# main.net
KiCad netlist of a schematic drawn in Altium Designer
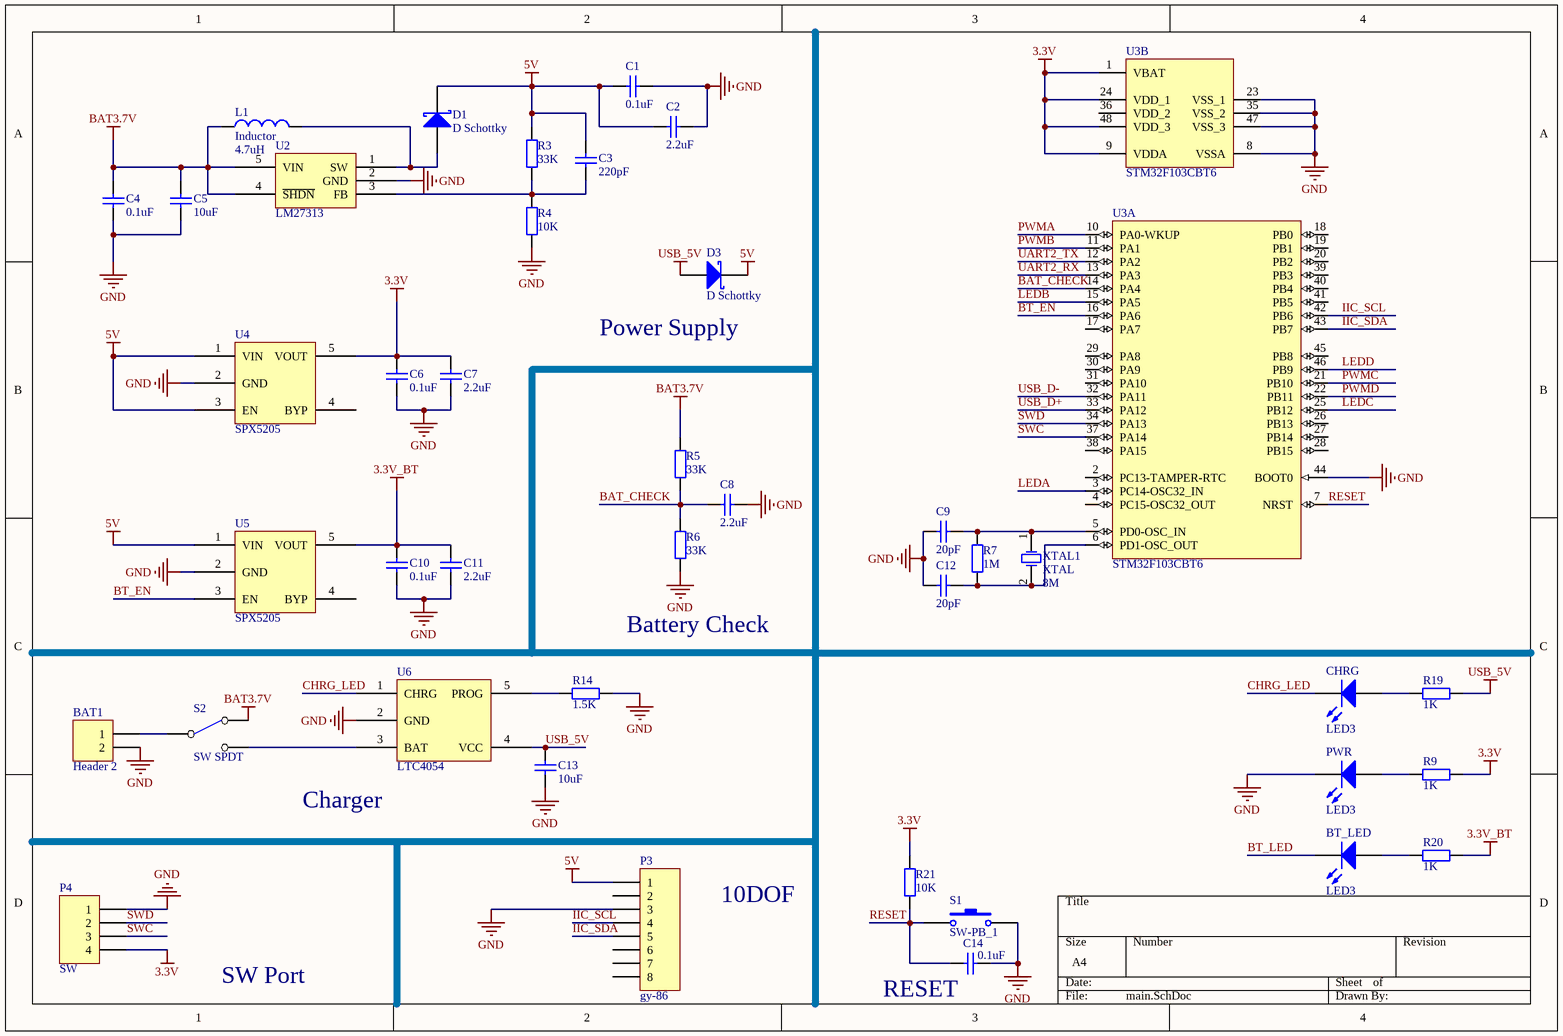
[diagram p0: main.SchDoc]

(export (version "E")
  (design (tool "Eeschema 10.0.6"))
  (components
    (comp (ref "BAT1")
      (value "Header 2")
      (footprint "HDR1*2 battery")
      (description "Header, 2-Pin")
      (fields (field (name "PUBLISHER") "Altium Limited"))
      (libsource (lib "Miscellaneous Connectors") (part "Header 2"))
    )
    (comp (ref "BT_LED")
      (value "LED3")
      (footprint "LED_0603_RED")
      (description "Typical BLUE SiC LED")
      (fields (field (name "PUBLISHER") "Altium Limited"))
      (libsource (lib "Miscellaneous Devices") (part "LED3"))
    )
    (comp (ref "C1")
      (value "0.1uF")
      (footprint "C-0603")
      (description "Capacitor (Semiconductor SIM Model)")
      (fields (field (name "Comment") "Cap Semi") (field (name "PUBLISHER") "Altium Limited"))
      (libsource (lib "Miscellaneous Devices") (part "Cap Semi"))
    )
    (comp (ref "C2")
      (value "2.2uF")
      (footprint "C-0603")
      (description "Capacitor (Semiconductor SIM Model)")
      (fields (field (name "Comment") "Cap Semi") (field (name "PUBLISHER") "Altium Limited"))
      (libsource (lib "Miscellaneous Devices") (part "Cap Semi"))
    )
    (comp (ref "C3")
      (value "220pF")
      (footprint "C-0603")
      (description "Capacitor (Semiconductor SIM Model)")
      (fields (field (name "Comment") "Cap Semi") (field (name "PUBLISHER") "Altium Limited"))
      (libsource (lib "Miscellaneous Devices") (part "Cap Semi"))
    )
    (comp (ref "C4")
      (value "0.1uF")
      (footprint "C-0603")
      (description "Capacitor (Semiconductor SIM Model)")
      (fields (field (name "Comment") "Cap Semi") (field (name "PUBLISHER") "Altium Limited"))
      (libsource (lib "Miscellaneous Devices") (part "Cap Semi"))
    )
    (comp (ref "C5")
      (value "10uF")
      (footprint "C-0603")
      (description "Capacitor (Semiconductor SIM Model)")
      (fields (field (name "Comment") "Cap Semi") (field (name "PUBLISHER") "Altium Limited"))
      (libsource (lib "Miscellaneous Devices") (part "Cap Semi"))
    )
    (comp (ref "C6")
      (value "0.1uF")
      (footprint "C-0603")
      (description "Capacitor (Semiconductor SIM Model)")
      (fields (field (name "Comment") "Cap Semi") (field (name "PUBLISHER") "Altium Limited"))
      (libsource (lib "Miscellaneous Devices") (part "Cap Semi"))
    )
    (comp (ref "C7")
      (value "2.2uF")
      (footprint "C-0603")
      (description "Capacitor (Semiconductor SIM Model)")
      (fields (field (name "Comment") "Cap Semi") (field (name "PUBLISHER") "Altium Limited"))
      (libsource (lib "Miscellaneous Devices") (part "Cap Semi"))
    )
    (comp (ref "C8")
      (value "2.2uF")
      (footprint "C-0603")
      (description "Capacitor (Semiconductor SIM Model)")
      (fields (field (name "Comment") "Cap Semi") (field (name "PUBLISHER") "Altium Limited"))
      (libsource (lib "Miscellaneous Devices") (part "Cap Semi"))
    )
    (comp (ref "C9")
      (value "20pF")
      (footprint "C-0603")
      (description "Capacitor (Semiconductor SIM Model)")
      (fields (field (name "Comment") "Cap") (field (name "PUBLISHER") "Altium Limited"))
      (libsource (lib "Miscellaneous Devices") (part "Cap Semi"))
    )
    (comp (ref "C10")
      (value "0.1uF")
      (footprint "C-0603")
      (description "Capacitor (Semiconductor SIM Model)")
      (fields (field (name "Comment") "Cap Semi") (field (name "PUBLISHER") "Altium Limited"))
      (libsource (lib "Miscellaneous Devices") (part "Cap Semi"))
    )
    (comp (ref "C11")
      (value "2.2uF")
      (footprint "C-0603")
      (description "Capacitor (Semiconductor SIM Model)")
      (fields (field (name "Comment") "Cap Semi") (field (name "PUBLISHER") "Altium Limited"))
      (libsource (lib "Miscellaneous Devices") (part "Cap Semi"))
    )
    (comp (ref "C12")
      (value "20pF")
      (footprint "C-0603")
      (description "Capacitor (Semiconductor SIM Model)")
      (fields (field (name "Comment") "Cap") (field (name "PUBLISHER") "Altium Limited"))
      (libsource (lib "Miscellaneous Devices") (part "Cap Semi"))
    )
    (comp (ref "C13")
      (value "10uF")
      (footprint "C-0603")
      (description "Capacitor (Semiconductor SIM Model)")
      (fields (field (name "Comment") "Cap Semi") (field (name "PUBLISHER") "Altium Limited"))
      (libsource (lib "Miscellaneous Devices") (part "Cap Semi"))
    )
    (comp (ref "C14")
      (value "0.1uF")
      (footprint "C-0603")
      (description "Capacitor (Semiconductor SIM Model)")
      (fields (field (name "Comment") "Cap") (field (name "PUBLISHER") "Altium Limited"))
      (libsource (lib "Miscellaneous Devices") (part "Cap Semi"))
    )
    (comp (ref "CHRG")
      (value "LED3")
      (footprint "LED_0603_RED")
      (description "Typical BLUE SiC LED")
      (fields (field (name "PUBLISHER") "Altium Limited"))
      (libsource (lib "Miscellaneous Devices") (part "LED3"))
    )
    (comp (ref "D1")
      (value "D Schottky")
      (footprint "DIODE-1206")
      (description "Schottky Diode")
      (fields (field (name "PUBLISHER") "Altium Limited"))
      (libsource (lib "Miscellaneous Devices") (part "D Schottky"))
    )
    (comp (ref "D3")
      (value "D Schottky")
      (footprint "DIODE-1206")
      (description "Schottky Diode")
      (fields (field (name "PUBLISHER") "Altium Limited"))
      (libsource (lib "Miscellaneous Devices") (part "D Schottky"))
    )
    (comp (ref "L1")
      (value "Inductor")
      (footprint "L-SMD-7")
      (fields (field (name "ALTIUM_VALUE") "4.7uH") (field (name "PUBLISHER") "Altium Limited"))
      (libsource (lib "Miscellaneous Devices") (part "Inductor"))
    )
    (comp (ref "P3")
      (value "gy-86")
      (footprint "HDR1X8")
      (description "Header, 8-Pin")
      (fields (field (name "PUBLISHER") "Altium Limited"))
      (libsource (lib "Miscellaneous Connectors") (part "Header 8"))
    )
    (comp (ref "P4")
      (value "SW")
      (footprint "HDR1X4")
      (description "Header, 4-Pin")
      (fields (field (name "PUBLISHER") "Altium Limited"))
      (libsource (lib "Miscellaneous Connectors") (part "Header 4"))
    )
    (comp (ref "PWR")
      (value "LED3")
      (footprint "LED_0603_RED")
      (description "Typical BLUE SiC LED")
      (fields (field (name "PUBLISHER") "Altium Limited"))
      (libsource (lib "Miscellaneous Devices") (part "LED3"))
    )
    (comp (ref "R3")
      (value "33K")
      (footprint "R-0603")
      (description "Resistor")
      (fields (field (name "Comment") "Res2") (field (name "PUBLISHER") "Altium Limited"))
      (libsource (lib "Miscellaneous Devices") (part "Res2"))
    )
    (comp (ref "R4")
      (value "10K")
      (footprint "R-0603")
      (description "Resistor")
      (fields (field (name "Comment") "Res2") (field (name "PUBLISHER") "Altium Limited"))
      (libsource (lib "Miscellaneous Devices") (part "Res2"))
    )
    (comp (ref "R5")
      (value "33K")
      (footprint "R-0603")
      (description "Resistor")
      (fields (field (name "Comment") "Res2") (field (name "PUBLISHER") "Altium Limited"))
      (libsource (lib "Miscellaneous Devices") (part "Res2"))
    )
    (comp (ref "R6")
      (value "33K")
      (footprint "R-0603")
      (description "Resistor")
      (fields (field (name "Comment") "Res2") (field (name "PUBLISHER") "Altium Limited"))
      (libsource (lib "Miscellaneous Devices") (part "Res2"))
    )
    (comp (ref "R7")
      (value "1M")
      (footprint "R-0603")
      (description "Resistor")
      (fields (field (name "Comment") "Res2") (field (name "PUBLISHER") "Altium Limited"))
      (libsource (lib "") (part "Res2_1"))
    )
    (comp (ref "R9")
      (value "1K")
      (footprint "R-0603")
      (description "Resistor")
      (fields (field (name "Comment") "Res2") (field (name "PUBLISHER") "Altium Limited"))
      (libsource (lib "Miscellaneous Devices") (part "Res2"))
    )
    (comp (ref "R14")
      (value "1.5K")
      (footprint "R-0603")
      (description "Resistor")
      (fields (field (name "Comment") "Res2") (field (name "PUBLISHER") "Altium Limited"))
      (libsource (lib "") (part "Res2_1"))
    )
    (comp (ref "R19")
      (value "1K")
      (footprint "R-0603")
      (description "Resistor")
      (fields (field (name "Comment") "Res2") (field (name "PUBLISHER") "Altium Limited"))
      (libsource (lib "Miscellaneous Devices") (part "Res2"))
    )
    (comp (ref "R20")
      (value "1K")
      (footprint "R-0603")
      (description "Resistor")
      (fields (field (name "Comment") "Res2") (field (name "PUBLISHER") "Altium Limited"))
      (libsource (lib "Miscellaneous Devices") (part "Res2"))
    )
    (comp (ref "R21")
      (value "10K")
      (footprint "R-0603")
      (description "Resistor")
      (fields (field (name "Comment") "Res2") (field (name "PUBLISHER") "Altium Limited"))
      (libsource (lib "") (part "Res2_2"))
    )
    (comp (ref "S1")
      (value "SW-PB_1")
      (footprint "SW-2-6*3")
      (description "Switch")
      (fields (field (name "PUBLISHER") "Altium Limited"))
      (libsource (lib "mcu_board") (part "SW-PB_1"))
    )
    (comp (ref "S2") (value "SW SPDT") (footprint "SW-SPDT 2mm") (libsource (lib "MOS_H") (part "SW SPDT")))
    (comp (ref "U2") (value "LM27313") (footprint "SOT23-5") (libsource (lib "mcu_board") (part "LM27313")))
    (comp (ref "U3")
      (value "STM32F103CBT6")
      (footprint "STM-LQFP48_M")
      (libsource (lib "STMicroelectronics STM32 F1") (part "STM32F103CBT6"))
    )
    (comp (ref "U4") (value "SPX5205") (footprint "SOT23-5") (libsource (lib "mcu_board") (part "SPX5205")))
    (comp (ref "U5") (value "SPX5205") (footprint "SOT23-5") (libsource (lib "mcu_board") (part "SPX5205")))
    (comp (ref "U6") (value "LTC4054") (footprint "SOT23-5") (libsource (lib "mcu_board") (part "LTC4054")))
    (comp (ref "XTAL1")
      (value "XTAL")
      (footprint "XTAL-QC49/SMD")
      (fields (field (name "FREQUENCE") "8M"))
      (libsource (lib "mcu_board") (part "XTAL"))
    )
  )
  (nets
    (net (code "1") (name "/BAT_CHECK") (class "Default")
      (node (ref "C8") (pin "2") (pinfunction "2_2") (pintype "passive"))
      (node (ref "R5") (pin "1") (pinfunction "1_1") (pintype "passive"))
      (node (ref "R6") (pin "2") (pinfunction "2_2") (pintype "passive"))
      (node (ref "U3") (pin "14") (pinfunction "PA4_14") (pintype "bidirectional"))
    )
    (net (code "2") (name "/BT_EN") (class "Default")
      (node (ref "U3") (pin "16") (pinfunction "PA6_16") (pintype "bidirectional"))
      (node (ref "U5") (pin "3") (pinfunction "EN_3") (pintype "passive"))
    )
    (net (code "3") (name "/BT_LED") (class "Default")
      (node (ref "BT_LED") (pin "2") (pinfunction "K_2") (pintype "passive"))
    )
    (net (code "4") (name "/CHRG_LED") (class "Default")
      (node (ref "CHRG") (pin "2") (pinfunction "K_2") (pintype "passive"))
      (node (ref "U6") (pin "1") (pinfunction "CHRG_1") (pintype "passive"))
    )
    (net (code "5") (name "/IIC_SCL") (class "Default")
      (node (ref "P3") (pin "4") (pinfunction "4_4") (pintype "passive"))
      (node (ref "U3") (pin "42") (pinfunction "PB6_42") (pintype "bidirectional"))
    )
    (net (code "6") (name "/IIC_SDA") (class "Default")
      (node (ref "P3") (pin "5") (pinfunction "5_5") (pintype "passive"))
      (node (ref "U3") (pin "43") (pinfunction "PB7_43") (pintype "bidirectional"))
    )
    (net (code "7") (name "/LEDA") (class "Default")
      (node (ref "U3") (pin "3") (pinfunction "PC14-OSC32_IN_3") (pintype "bidirectional"))
    )
    (net (code "8") (name "/LEDB") (class "Default")
      (node (ref "U3") (pin "15") (pinfunction "PA5_15") (pintype "bidirectional"))
    )
    (net (code "9") (name "/LEDC") (class "Default")
      (node (ref "U3") (pin "25") (pinfunction "PB12_25") (pintype "bidirectional"))
    )
    (net (code "10") (name "/LEDD") (class "Default")
      (node (ref "U3") (pin "46") (pinfunction "PB9_46") (pintype "bidirectional"))
    )
    (net (code "11") (name "/PWMA") (class "Default")
      (node (ref "U3") (pin "10") (pinfunction "PA0-WKUP_10") (pintype "bidirectional"))
    )
    (net (code "12") (name "/PWMB") (class "Default")
      (node (ref "U3") (pin "11") (pinfunction "PA1_11") (pintype "bidirectional"))
    )
    (net (code "13") (name "/PWMC") (class "Default")
      (node (ref "U3") (pin "21") (pinfunction "PB10_21") (pintype "bidirectional"))
    )
    (net (code "14") (name "/PWMD") (class "Default")
      (node (ref "U3") (pin "22") (pinfunction "PB11_22") (pintype "bidirectional"))
    )
    (net (code "15") (name "/RESET") (class "Default")
      (node (ref "C14") (pin "2") (pinfunction "2_2") (pintype "passive"))
      (node (ref "R21") (pin "1") (pinfunction "1_1") (pintype "passive"))
      (node (ref "S1") (pin "1") (pinfunction "1_1") (pintype "passive"))
      (node (ref "U3") (pin "7") (pinfunction "NRST_7") (pintype "bidirectional"))
    )
    (net (code "16") (name "/SWC") (class "Default")
      (node (ref "P4") (pin "3") (pinfunction "3_3") (pintype "passive"))
      (node (ref "U3") (pin "37") (pinfunction "PA14_37") (pintype "bidirectional"))
    )
    (net (code "17") (name "/SWD") (class "Default")
      (node (ref "P4") (pin "2") (pinfunction "2_2") (pintype "passive"))
      (node (ref "U3") (pin "34") (pinfunction "PA13_34") (pintype "bidirectional"))
    )
    (net (code "18") (name "/UART2_RX") (class "Default")
      (node (ref "U3") (pin "13") (pinfunction "PA3_13") (pintype "bidirectional"))
    )
    (net (code "19") (name "/UART2_TX") (class "Default")
      (node (ref "U3") (pin "12") (pinfunction "PA2_12") (pintype "bidirectional"))
    )
    (net (code "20") (name "/USB_D+") (class "Default")
      (node (ref "U3") (pin "33") (pinfunction "PA12_33") (pintype "bidirectional"))
    )
    (net (code "21") (name "/USB_D-") (class "Default")
      (node (ref "U3") (pin "32") (pinfunction "PA11_32") (pintype "bidirectional"))
    )
    (net (code "22") (name "3.3V") (class "Default")
      (node (ref "C6") (pin "1") (pinfunction "1_1") (pintype "passive"))
      (node (ref "C7") (pin "1") (pinfunction "1_1") (pintype "passive"))
      (node (ref "P4") (pin "4") (pinfunction "4_4") (pintype "power_in"))
      (node (ref "R21") (pin "2") (pinfunction "2_2") (pintype "passive"))
      (node (ref "R9") (pin "2") (pinfunction "2_2") (pintype "passive"))
      (node (ref "U3") (pin "1") (pinfunction "VBAT_1") (pintype "power_in"))
      (node (ref "U3") (pin "24") (pinfunction "VDD_1_24") (pintype "power_in"))
      (node (ref "U3") (pin "48") (pinfunction "VDD_3_48") (pintype "power_in"))
      (node (ref "U3") (pin "9") (pinfunction "VDDA_9") (pintype "power_in"))
      (node (ref "U4") (pin "5") (pinfunction "VOUT_5") (pintype "passive"))
    )
    (net (code "23") (name "3.3V_BT") (class "Default")
      (node (ref "C10") (pin "1") (pinfunction "1_1") (pintype "passive"))
      (node (ref "C11") (pin "1") (pinfunction "1_1") (pintype "passive"))
      (node (ref "R20") (pin "2") (pinfunction "2_2") (pintype "passive"))
      (node (ref "U5") (pin "5") (pinfunction "VOUT_5") (pintype "passive"))
    )
    (net (code "24") (name "5V") (class "Default")
      (node (ref "C1") (pin "1") (pinfunction "1_1") (pintype "passive"))
      (node (ref "C2") (pin "1") (pinfunction "1_1") (pintype "passive"))
      (node (ref "C3") (pin "2") (pinfunction "2_2") (pintype "passive"))
      (node (ref "D1") (pin "2") (pinfunction "K_2") (pintype "passive"))
      (node (ref "D3") (pin "2") (pinfunction "K_2") (pintype "passive"))
      (node (ref "P3") (pin "1") (pinfunction "1_1") (pintype "passive"))
      (node (ref "R3") (pin "2") (pinfunction "2_2") (pintype "passive"))
      (node (ref "U4") (pin "1") (pinfunction "VIN_1") (pintype "passive"))
      (node (ref "U4") (pin "3") (pinfunction "EN_3") (pintype "passive"))
      (node (ref "U5") (pin "1") (pinfunction "VIN_1") (pintype "passive"))
    )
    (net (code "25") (name "BAT3.7V") (class "Default")
      (node (ref "C4") (pin "2") (pinfunction "2_2") (pintype "passive"))
      (node (ref "C5") (pin "2") (pinfunction "2_2") (pintype "passive"))
      (node (ref "L1") (pin "1") (pinfunction "1_1") (pintype "passive"))
      (node (ref "R5") (pin "2") (pinfunction "2_2") (pintype "passive"))
      (node (ref "S2") (pin "1") (pinfunction "NC_1") (pintype "passive"))
      (node (ref "U2") (pin "4") (pinfunction "~{SHDN}_4") (pintype "passive"))
      (node (ref "U2") (pin "5") (pinfunction "VIN_5") (pintype "passive"))
    )
    (net (code "26") (name "GND") (class "Default")
      (node (ref "BAT1") (pin "2") (pinfunction "2_2") (pintype "power_in"))
      (node (ref "C1") (pin "2") (pinfunction "2_2") (pintype "passive"))
      (node (ref "C10") (pin "2") (pinfunction "2_2") (pintype "passive"))
      (node (ref "C11") (pin "2") (pinfunction "2_2") (pintype "passive"))
      (node (ref "C12") (pin "2") (pinfunction "2_2") (pintype "passive"))
      (node (ref "C13") (pin "2") (pinfunction "2_2") (pintype "passive"))
      (node (ref "C14") (pin "1") (pinfunction "1_1") (pintype "passive"))
      (node (ref "C2") (pin "2") (pinfunction "2_2") (pintype "passive"))
      (node (ref "C4") (pin "1") (pinfunction "1_1") (pintype "passive"))
      (node (ref "C5") (pin "1") (pinfunction "1_1") (pintype "passive"))
      (node (ref "C6") (pin "2") (pinfunction "2_2") (pintype "passive"))
      (node (ref "C7") (pin "2") (pinfunction "2_2") (pintype "passive"))
      (node (ref "C8") (pin "1") (pinfunction "1_1") (pintype "passive"))
      (node (ref "C9") (pin "2") (pinfunction "2_2") (pintype "passive"))
      (node (ref "P3") (pin "3") (pinfunction "3_3") (pintype "passive"))
      (node (ref "P4") (pin "1") (pinfunction "1_1") (pintype "passive"))
      (node (ref "PWR") (pin "2") (pinfunction "K_2") (pintype "passive"))
      (node (ref "R14") (pin "1") (pinfunction "1_1") (pintype "passive"))
      (node (ref "R4") (pin "1") (pinfunction "1_1") (pintype "passive"))
      (node (ref "R6") (pin "1") (pinfunction "1_1") (pintype "passive"))
      (node (ref "S1") (pin "2") (pinfunction "2_2") (pintype "passive"))
      (node (ref "U2") (pin "2") (pinfunction "GND_2") (pintype "passive"))
      (node (ref "U3") (pin "23") (pinfunction "VSS_1_23") (pintype "power_in"))
      (node (ref "U3") (pin "35") (pinfunction "VSS_2_35") (pintype "power_in"))
      (node (ref "U3") (pin "44") (pinfunction "BOOT0_44") (pintype "input"))
      (node (ref "U3") (pin "47") (pinfunction "VSS_3_47") (pintype "power_in"))
      (node (ref "U3") (pin "8") (pinfunction "VSSA_8") (pintype "power_in"))
      (node (ref "U4") (pin "2") (pinfunction "GND_2") (pintype "passive"))
      (node (ref "U5") (pin "2") (pinfunction "GND_2") (pintype "passive"))
      (node (ref "U6") (pin "2") (pinfunction "GND_2") (pintype "passive"))
    )
    (net (code "27") (name "Net-(BT_LED-A)") (class "Default")
      (node (ref "BT_LED") (pin "1") (pinfunction "A_1") (pintype "passive"))
      (node (ref "R20") (pin "1") (pinfunction "1_1") (pintype "passive"))
    )
    (net (code "28") (name "Net-(CHRG-A)") (class "Default")
      (node (ref "CHRG") (pin "1") (pinfunction "A_1") (pintype "passive"))
      (node (ref "R19") (pin "1") (pinfunction "1_1") (pintype "passive"))
    )
    (net (code "29") (name "Net-(D1-A)") (class "Default")
      (node (ref "D1") (pin "1") (pinfunction "A_1") (pintype "passive"))
      (node (ref "L1") (pin "2") (pinfunction "2_2") (pintype "passive"))
      (node (ref "U2") (pin "1") (pinfunction "SW_1") (pintype "passive"))
    )
    (net (code "30") (name "Net-(PWR-A)") (class "Default")
      (node (ref "PWR") (pin "1") (pinfunction "A_1") (pintype "passive"))
      (node (ref "R9") (pin "1") (pinfunction "1_1") (pintype "passive"))
    )
    (net (code "31") (name "Net-(S2-COMMON)") (class "Default")
      (node (ref "BAT1") (pin "1") (pinfunction "1_1") (pintype "power_in"))
      (node (ref "S2") (pin "2") (pinfunction "COMMON_2") (pintype "passive"))
    )
    (net (code "32") (name "Net-(S2-NO)") (class "Default")
      (node (ref "S2") (pin "3") (pinfunction "NO_3") (pintype "passive"))
      (node (ref "U6") (pin "3") (pinfunction "BAT_3") (pintype "passive"))
    )
    (net (code "33") (name "Net-(U2-FB)") (class "Default")
      (node (ref "C3") (pin "1") (pinfunction "1_1") (pintype "passive"))
      (node (ref "R3") (pin "1") (pinfunction "1_1") (pintype "passive"))
      (node (ref "R4") (pin "2") (pinfunction "2_2") (pintype "passive"))
      (node (ref "U2") (pin "3") (pinfunction "FB_3") (pintype "passive"))
    )
    (net (code "34") (name "Net-(U3A-PD0-OSC_IN)") (class "Default")
      (node (ref "C9") (pin "1") (pinfunction "1_1") (pintype "passive"))
      (node (ref "R7") (pin "1") (pinfunction "1_1") (pintype "passive"))
      (node (ref "U3") (pin "5") (pinfunction "PD0-OSC_IN_5") (pintype "bidirectional"))
      (node (ref "XTAL1") (pin "1") (pinfunction "1_1") (pintype "passive"))
    )
    (net (code "35") (name "Net-(U3A-PD1-OSC_OUT)") (class "Default")
      (node (ref "C12") (pin "1") (pinfunction "1_1") (pintype "passive"))
      (node (ref "R7") (pin "2") (pinfunction "2_2") (pintype "passive"))
      (node (ref "U3") (pin "6") (pinfunction "PD1-OSC_OUT_6") (pintype "bidirectional"))
      (node (ref "XTAL1") (pin "2") (pinfunction "2_2") (pintype "passive"))
    )
    (net (code "36") (name "Net-(U6-PROG)") (class "Default")
      (node (ref "R14") (pin "2") (pinfunction "2_2") (pintype "passive"))
      (node (ref "U6") (pin "5") (pinfunction "PROG_5") (pintype "passive"))
    )
    (net (code "37") (name "USB_5V") (class "Default")
      (node (ref "C13") (pin "1") (pinfunction "1_1") (pintype "passive"))
      (node (ref "D3") (pin "1") (pinfunction "A_1") (pintype "passive"))
      (node (ref "R19") (pin "2") (pinfunction "2_2") (pintype "passive"))
      (node (ref "U6") (pin "4") (pinfunction "VCC_4") (pintype "passive"))
    )
    (net (code "38") (name "unconnected-(P3-Pad2)") (class "Default")
      (node (ref "P3") (pin "2") (pinfunction "2_2") (pintype "passive"))
    )
    (net (code "39") (name "unconnected-(P3-Pad6)") (class "Default")
      (node (ref "P3") (pin "6") (pinfunction "6_6") (pintype "passive"))
    )
    (net (code "40") (name "unconnected-(P3-Pad7)") (class "Default")
      (node (ref "P3") (pin "7") (pinfunction "7_7") (pintype "passive"))
    )
    (net (code "41") (name "unconnected-(P3-Pad8)") (class "Default")
      (node (ref "P3") (pin "8") (pinfunction "8_8") (pintype "passive"))
    )
    (net (code "42") (name "unconnected-(U3A-PA7-Pad17)") (class "Default")
      (node (ref "U3") (pin "17") (pinfunction "PA7_17") (pintype "bidirectional"))
    )
    (net (code "43") (name "unconnected-(U3A-PA8-Pad29)") (class "Default")
      (node (ref "U3") (pin "29") (pinfunction "PA8_29") (pintype "bidirectional"))
    )
    (net (code "44") (name "unconnected-(U3A-PA9-Pad30)") (class "Default")
      (node (ref "U3") (pin "30") (pinfunction "PA9_30") (pintype "bidirectional"))
    )
    (net (code "45") (name "unconnected-(U3A-PA10-Pad31)") (class "Default")
      (node (ref "U3") (pin "31") (pinfunction "PA10_31") (pintype "bidirectional"))
    )
    (net (code "46") (name "unconnected-(U3A-PA15-Pad38)") (class "Default")
      (node (ref "U3") (pin "38") (pinfunction "PA15_38") (pintype "bidirectional"))
    )
    (net (code "47") (name "unconnected-(U3A-PB0-Pad18)") (class "Default")
      (node (ref "U3") (pin "18") (pinfunction "PB0_18") (pintype "bidirectional"))
    )
    (net (code "48") (name "unconnected-(U3A-PB1-Pad19)") (class "Default")
      (node (ref "U3") (pin "19") (pinfunction "PB1_19") (pintype "bidirectional"))
    )
    (net (code "49") (name "unconnected-(U3A-PB2-Pad20)") (class "Default")
      (node (ref "U3") (pin "20") (pinfunction "PB2_20") (pintype "bidirectional"))
    )
    (net (code "50") (name "unconnected-(U3A-PB3-Pad39)") (class "Default")
      (node (ref "U3") (pin "39") (pinfunction "PB3_39") (pintype "bidirectional"))
    )
    (net (code "51") (name "unconnected-(U3A-PB4-Pad40)") (class "Default")
      (node (ref "U3") (pin "40") (pinfunction "PB4_40") (pintype "bidirectional"))
    )
    (net (code "52") (name "unconnected-(U3A-PB5-Pad41)") (class "Default")
      (node (ref "U3") (pin "41") (pinfunction "PB5_41") (pintype "bidirectional"))
    )
    (net (code "53") (name "unconnected-(U3A-PB8-Pad45)") (class "Default")
      (node (ref "U3") (pin "45") (pinfunction "PB8_45") (pintype "bidirectional"))
    )
    (net (code "54") (name "unconnected-(U3A-PB13-Pad26)") (class "Default")
      (node (ref "U3") (pin "26") (pinfunction "PB13_26") (pintype "bidirectional"))
    )
    (net (code "55") (name "unconnected-(U3A-PB14-Pad27)") (class "Default")
      (node (ref "U3") (pin "27") (pinfunction "PB14_27") (pintype "bidirectional"))
    )
    (net (code "56") (name "unconnected-(U3A-PB15-Pad28)") (class "Default")
      (node (ref "U3") (pin "28") (pinfunction "PB15_28") (pintype "bidirectional"))
    )
    (net (code "57") (name "unconnected-(U3A-PC13-TAMPER-RTC-Pad2)") (class "Default")
      (node (ref "U3") (pin "2") (pinfunction "PC13-TAMPER-RTC_2") (pintype "bidirectional"))
    )
    (net (code "58") (name "unconnected-(U3A-PC15-OSC32_OUT-Pad4)") (class "Default")
      (node (ref "U3") (pin "4") (pinfunction "PC15-OSC32_OUT_4") (pintype "bidirectional"))
    )
    (net (code "59") (name "unconnected-(U3B-VDD_2-Pad36)") (class "Default")
      (node (ref "U3") (pin "36") (pinfunction "VDD_2_36") (pintype "power_in"))
    )
    (net (code "60") (name "unconnected-(U4-BYP-Pad4)") (class "Default")
      (node (ref "U4") (pin "4") (pinfunction "BYP_4") (pintype "passive"))
    )
    (net (code "61") (name "unconnected-(U5-BYP-Pad4)") (class "Default")
      (node (ref "U5") (pin "4") (pinfunction "BYP_4") (pintype "passive"))
    )
  )
)
